# MCU.net
KiCad netlist of a schematic drawn in Altium Designer
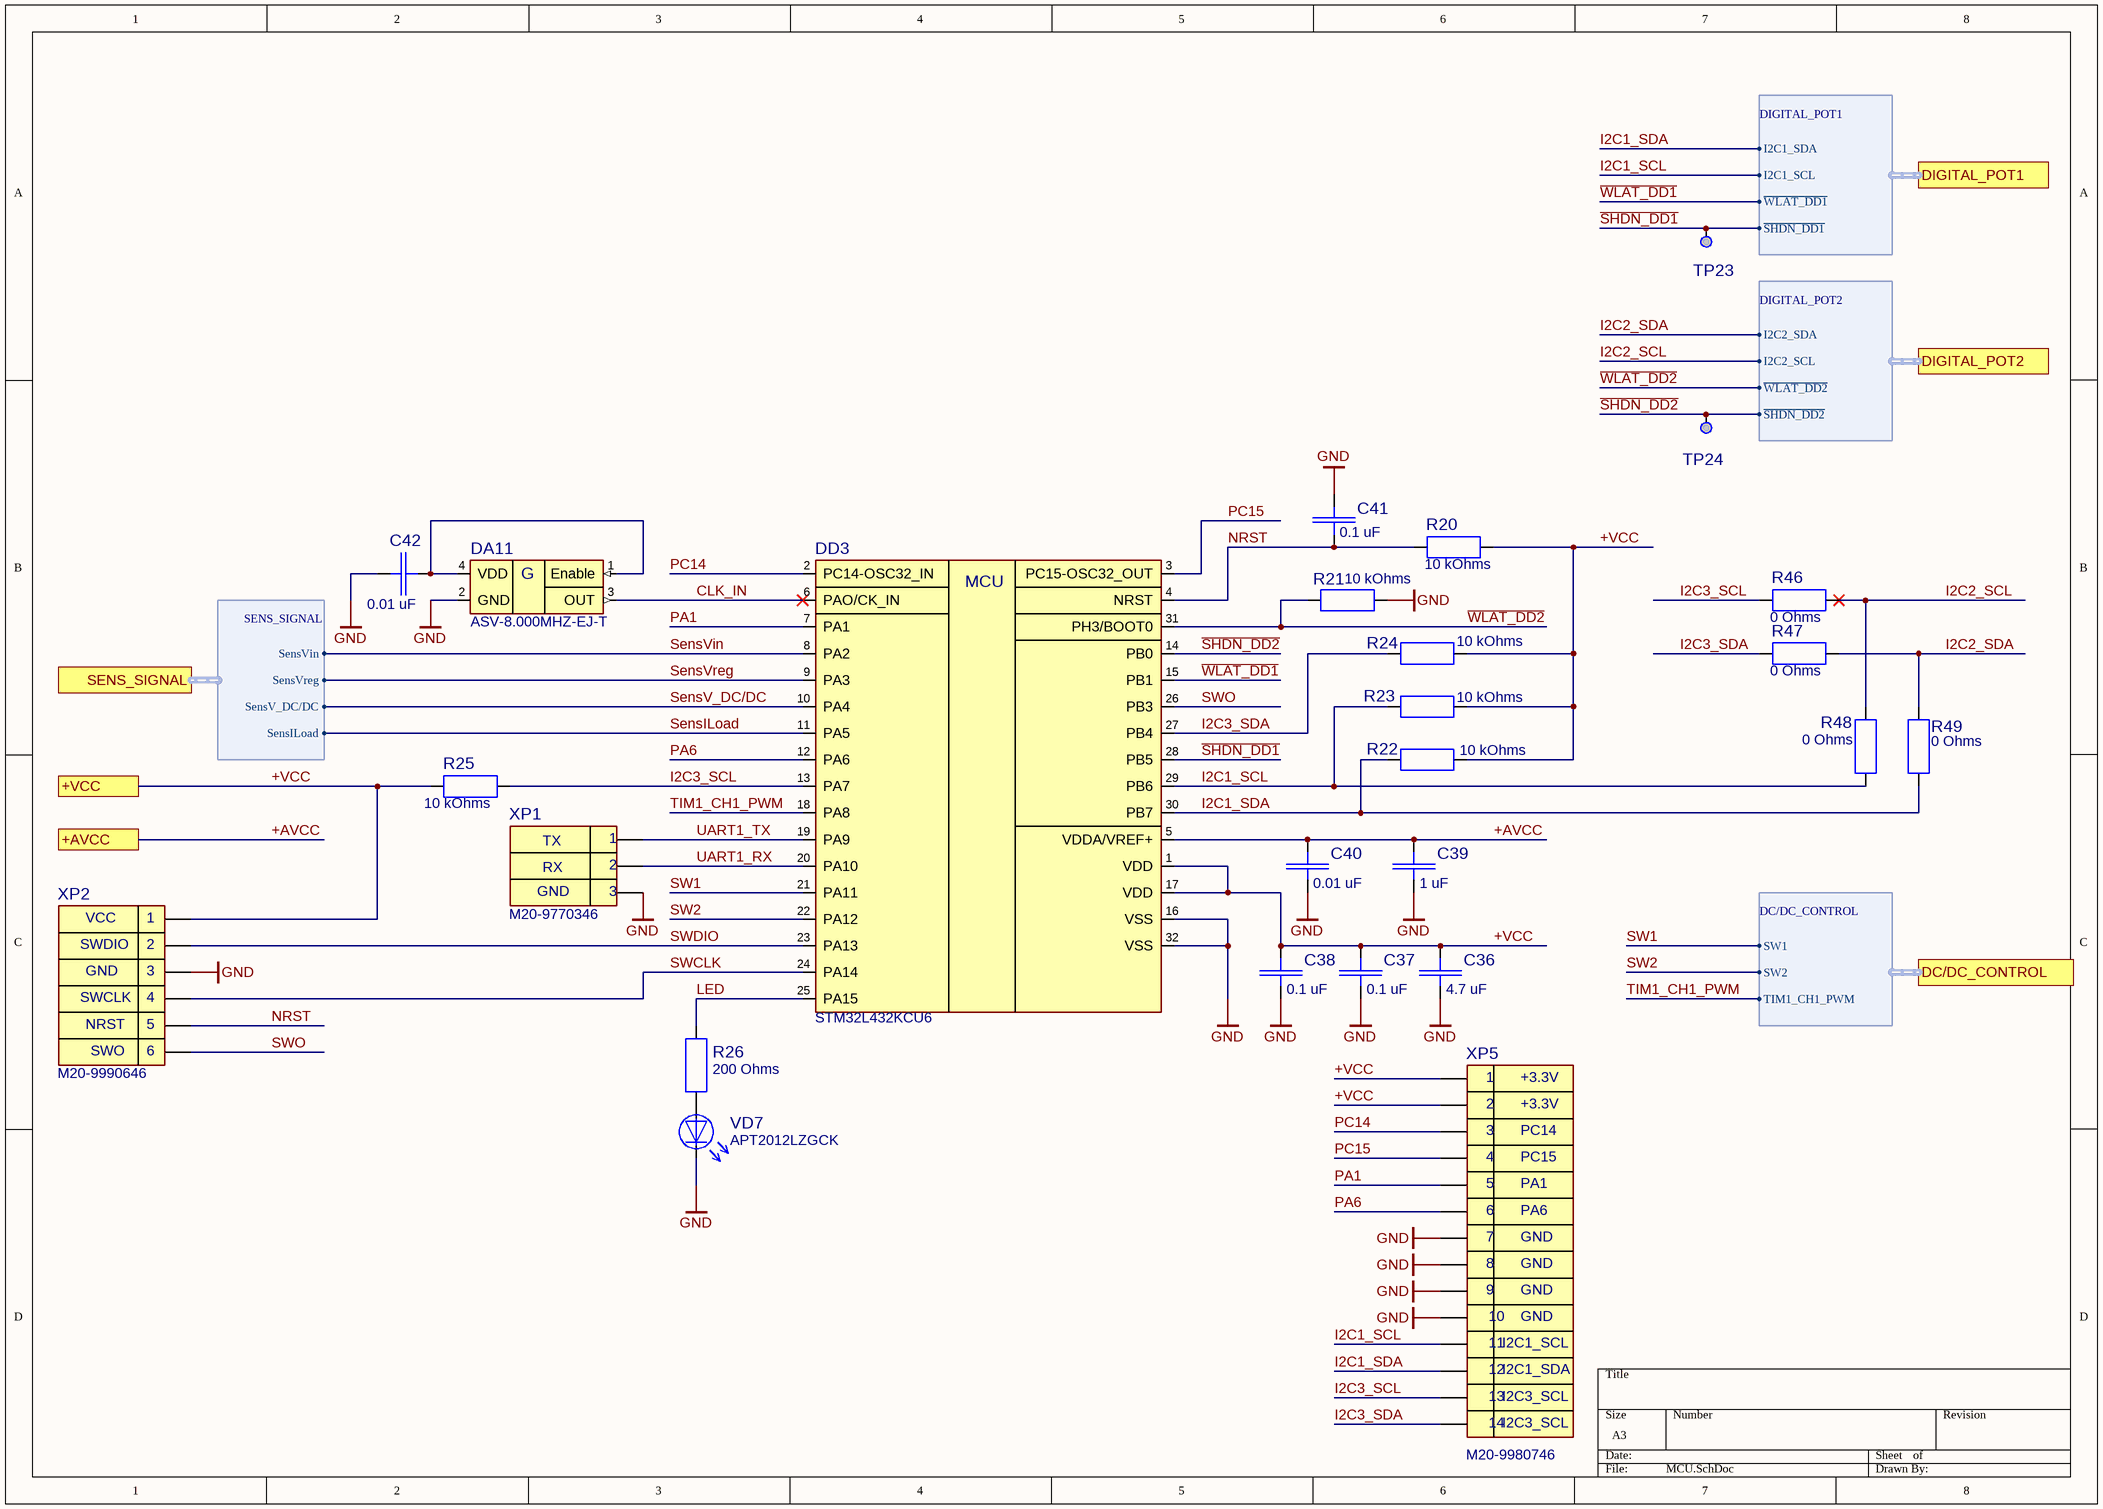
[diagram p0: MCU.SchDoc]

(export (version "E")
  (design (tool "Eeschema 10.0.6"))
  (components
    (comp (ref "C36")
      (value "4.7 uF")
      (footprint "Capacitor0805_THICKNESS1.25")
      (description "Multilayer Ceramic Capacitors MLCC - SMD/SMT 4.7uF+/-10% 25V X5R 0805")
      (fields
        (field (name "MANUFACTURER") "Samsung Electro-Mechanics")
        (field (name "MANUFACTURERPARTNUMBER") "CL21A475KAQNNNF")
      )
      (libsource (lib "NGI_Search") (part "CL21A475KAQNNNF"))
    )
    (comp (ref "C37")
      (value "0.1 uF")
      (footprint "Capacitor0805_THICKNESS0.8")
      (description "Multilayer Ceramic Capacitors MLCC - SMD/SMT 100nF+/-10% 50V X7R 0805")
      (fields (field (name "TOLERANCE") "10%") (field (name "MANUFACTURERPARTNUMBER") "CL21B104KBCNNWC"))
      (libsource (lib "NGI_Search") (part "CL21B104KBCNNWC"))
    )
    (comp (ref "C38")
      (value "0.1 uF")
      (footprint "Capacitor0805_THICKNESS0.8")
      (description "Multilayer Ceramic Capacitors MLCC - SMD/SMT 100nF+/-10% 50V X7R 0805")
      (fields (field (name "TOLERANCE") "10%") (field (name "MANUFACTURERPARTNUMBER") "CL21B104KBCNNWC"))
      (libsource (lib "NGI_Search") (part "CL21B104KBCNNWC"))
    )
    (comp (ref "C39")
      (value "1 uF")
      (footprint "Capacitor0805_THICKNESS1.25")
      (description "Multilayer Ceramic Capacitors MLCC - SMD/SMT 1uF+/-10% 25V X7R 20 0805")
      (fields
        (field (name "MANUFACTURER") "Samsung Electro-Mechanics")
        (field (name "MANUFACTURERPARTNUMBER") "CL21B105KAFNFNE")
      )
      (libsource (lib "NGI_Search") (part "CL21B105KAFNFNE"))
    )
    (comp (ref "C40")
      (value "0.01 uF")
      (footprint "Capacitor0805_THICKNESS0.8")
      (description "Multilayer Ceramic Capacitors MLCC - SMD/SMT 10nF+/-10% 50V X7R 2 0805")
      (fields
        (field (name "MANUFACTURER") "Samsung Electro-Mechanics")
        (field (name "MANUFACTURERPARTNUMBER") "CL21B103KBANNNL")
      )
      (libsource (lib "NGI_Search") (part "CL21B103KBANNNL"))
    )
    (comp (ref "C41")
      (value "0.1 uF")
      (footprint "Capacitor0805_THICKNESS0.8")
      (description "Multilayer Ceramic Capacitors MLCC - SMD/SMT 100nF+/-10% 50V X7R 0805")
      (fields (field (name "TOLERANCE") "10%") (field (name "MANUFACTURERPARTNUMBER") "CL21B104KBCNNWC"))
      (libsource (lib "NGI_Search") (part "CL21B104KBCNNWC"))
    )
    (comp (ref "C42")
      (value "0.01 uF")
      (footprint "Capacitor0805_THICKNESS0.8")
      (description "Multilayer Ceramic Capacitors MLCC - SMD/SMT 10nF+/-10% 50V X7R 2 0805")
      (fields
        (field (name "MANUFACTURER") "Samsung Electro-Mechanics")
        (field (name "MANUFACTURERPARTNUMBER") "CL21B103KBANNNL")
      )
      (libsource (lib "NGI_Search") (part "CL21B103KBANNNL"))
    )
    (comp (ref "DA11")
      (value "ASV-8.000MHZ-EJ-T")
      (footprint "HCMOS 7 mm x 5 mm")
      (description "Standard Clock Oscillators XTAL OSC XO 8.0000MHZ HCMOS SMD")
      (fields (field (name "MANUFACTURER") "ABRACON") (field (name "MOUSER PART NUMBER") "815-ASV-8-EJ-T"))
      (libsource (lib "NGI_Search") (part "ASV-8.000MHZ-EJ-T"))
    )
    (comp (ref "DD3")
      (value "STM32L432KCU6")
      (footprint "UFQFPN-32")
      (description "ARM Microcontrollers - MCU Ultra-low-power FPU Arm Cortex-M4 MCU 80 MHz 256 Kbytes of Flash , USB")
      (fields
        (field (name "MANUFACTURER") "STMicroelectronics")
        (field (name "MOUSER PART NUMBER") "511-STM32L432KCU6")
      )
      (libsource (lib "NGI_Search") (part "STM32L432KCU6"))
    )
    (comp (ref "R20")
      (value "10 kOhms")
      (footprint "Resistor0805_THICKNESS0.6")
      (description "Thick Film Resistors 10 kOhms 125 mW 0805 1%")
      (fields (field (name "MANUFACTURER") "YAGEO") (field (name "MANUFACTURERPARTNUMBER") "RC0805FR-0710KL"))
      (libsource (lib "NGI_Search") (part "RC0805FR-0710KL"))
    )
    (comp (ref "R21")
      (value "10 kOhms")
      (footprint "Resistor0805_THICKNESS0.6")
      (description "Thick Film Resistors 10 kOhms 125 mW 0805 1%")
      (fields (field (name "MANUFACTURER") "YAGEO") (field (name "MANUFACTURERPARTNUMBER") "RC0805FR-0710KL"))
      (libsource (lib "NGI_Search") (part "RC0805FR-0710KL"))
    )
    (comp (ref "R22")
      (value "10 kOhms")
      (footprint "Resistor0805_THICKNESS0.6")
      (description "Thick Film Resistors 10 kOhms 125 mW 0805 1%")
      (fields (field (name "MANUFACTURER") "YAGEO") (field (name "MANUFACTURERPARTNUMBER") "RC0805FR-0710KL"))
      (libsource (lib "NGI_Search") (part "RC0805FR-0710KL"))
    )
    (comp (ref "R23")
      (value "10 kOhms")
      (footprint "Resistor0805_THICKNESS0.6")
      (description "Thick Film Resistors 10 kOhms 125 mW 0805 1%")
      (fields (field (name "MANUFACTURER") "YAGEO") (field (name "MANUFACTURERPARTNUMBER") "RC0805FR-0710KL"))
      (libsource (lib "NGI_Search") (part "RC0805FR-0710KL"))
    )
    (comp (ref "R24")
      (value "10 kOhms")
      (footprint "Resistor0805_THICKNESS0.6")
      (description "Thick Film Resistors 10 kOhms 125 mW 0805 1%")
      (fields (field (name "MANUFACTURER") "YAGEO") (field (name "MANUFACTURERPARTNUMBER") "RC0805FR-0710KL"))
      (libsource (lib "NGI_Search") (part "RC0805FR-0710KL"))
    )
    (comp (ref "R25")
      (value "10 kOhms")
      (footprint "Resistor0805_THICKNESS0.6")
      (description "Thick Film Resistors 10 kOhms 125 mW 0805 1%")
      (fields (field (name "MANUFACTURER") "YAGEO") (field (name "MANUFACTURERPARTNUMBER") "RC0805FR-0710KL"))
      (libsource (lib "NGI_Search") (part "RC0805FR-0710KL"))
    )
    (comp (ref "R26")
      (value "200 Ohms")
      (footprint "Resistor0805_THICKNESS0.6")
      (description "Thick Film Resistors 200Ohms 1/8W 0805 1%")
      (fields
        (field (name "MANUFACTURER") "YAGEO")
        (field (name "MANUFACTURERPARTNUMBER") "RC0805FR-10200RL")
      )
      (libsource (lib "NGI_Search") (part "RC0805FR-10200RL"))
    )
    (comp (ref "R46")
      (value "0 Ohms")
      (footprint "Resistor0805_THICKNESS0.6")
      (description "Thick Film Resistors 0 Ohms 125 mW 0805 1%")
      (fields (field (name "MANUFACTURER") "YAGEO") (field (name "MANUFACTURERPARTNUMBER") "RC0805FR-070RL"))
      (libsource (lib "NGI_Search") (part "RC0805FR-070RL"))
    )
    (comp (ref "R47")
      (value "0 Ohms")
      (footprint "Resistor0805_THICKNESS0.6")
      (description "Thick Film Resistors 0 Ohms 125 mW 0805 1%")
      (fields (field (name "MANUFACTURER") "YAGEO") (field (name "MANUFACTURERPARTNUMBER") "RC0805FR-070RL"))
      (libsource (lib "NGI_Search") (part "RC0805FR-070RL"))
    )
    (comp (ref "R48")
      (value "0 Ohms")
      (footprint "Resistor0805_THICKNESS0.6")
      (description "Thick Film Resistors 0 Ohms 125 mW 0805 1%")
      (fields (field (name "MANUFACTURER") "YAGEO") (field (name "MANUFACTURERPARTNUMBER") "RC0805FR-070RL"))
      (libsource (lib "NGI_Search") (part "RC0805FR-070RL"))
    )
    (comp (ref "R49")
      (value "0 Ohms")
      (footprint "Resistor0805_THICKNESS0.6")
      (description "Thick Film Resistors 0 Ohms 125 mW 0805 1%")
      (fields (field (name "MANUFACTURER") "YAGEO") (field (name "MANUFACTURERPARTNUMBER") "RC0805FR-070RL"))
      (libsource (lib "NGI_Search") (part "RC0805FR-070RL"))
    )
    (comp (ref "TP23")
      (value "test point")
      (footprint "test point")
      (libsource (lib "NGI_Search") (part "test point"))
    )
    (comp (ref "TP24")
      (value "test point")
      (footprint "test point")
      (libsource (lib "NGI_Search") (part "test point"))
    )
    (comp (ref "VD7")
      (value "APT2012LZGCK")
      (footprint "APT2012LZGCK0805_LEDs")
      (description "Standard LEDs - SMD 2.0X1.2MM LOW CRNT")
      (fields
        (field (name "MANUFACTURER") "Kingbright")
        (field (name "MOUSER PART NUMBER") "604-APT2012LZGCK")
      )
      (libsource (lib "NGI_Search") (part "APT2012LZGCK"))
    )
    (comp (ref "XP1")
      (value "M20-9770346")
      (footprint "3 VERTICAL PIN Pitch: 2.54 mm")
      (description "Headers & Wire Housings 03 SIL VERTICAL PIN HEADER TIN")
      (fields (field (name "MANUFACTURER") "Harwin") (field (name "MOUSER PART NUMBER") "855-M20-9770346"))
      (libsource (lib "NGI_Search") (part "M20-9770346"))
    )
    (comp (ref "XP2")
      (value "M20-9990646")
      (footprint "6 VERTICAL PIN Pitch: 2.54 mm")
      (description "Headers & Wire Housings 06 SIL VERTICAL PIN HEADER TIN")
      (fields (field (name "MANUFACTURER") "Harwin"))
      (libsource (lib "NGI_Search") (part "M20-9990646"))
    )
    (comp (ref "XP5")
      (value "M20-9980746")
      (footprint "M20-9980746")
      (description "Headers & Wire Housings 07+07 DIL VERTICAL PIN HEADER TIN")
      (fields (field (name "MANUFACTURER") "Harwin") (field (name "MOUSER PART NUMBER") "855-M20-9980746"))
      (libsource (lib "NGI_Search") (part "M20-9980746"))
    )
  )
  (nets
    (net (code "5") (name "/+AVCC") (class "Default")
      (node (ref "C39") (pin "2") (pinfunction "2_2") (pintype "passive"))
      (node (ref "C40") (pin "2") (pinfunction "2_2") (pintype "passive"))
      (node (ref "DD3") (pin "5") (pinfunction "VDDA/VREF+_5") (pintype "power_in"))
    )
    (net (code "6") (name "/+VCC") (class "Default")
      (node (ref "C36") (pin "2") (pinfunction "2_2") (pintype "passive"))
      (node (ref "C37") (pin "2") (pinfunction "2_2") (pintype "passive"))
      (node (ref "C38") (pin "2") (pinfunction "2_2") (pintype "passive"))
      (node (ref "DD3") (pin "1") (pinfunction "VDD_1") (pintype "power_in"))
      (node (ref "DD3") (pin "17") (pinfunction "VDD_17") (pintype "power_in"))
      (node (ref "R20") (pin "2") (pinfunction "2_2") (pintype "passive"))
      (node (ref "R22") (pin "1") (pinfunction "1_1") (pintype "passive"))
      (node (ref "R23") (pin "2") (pinfunction "2_2") (pintype "passive"))
      (node (ref "R24") (pin "1") (pinfunction "1_1") (pintype "passive"))
      (node (ref "R25") (pin "1") (pinfunction "1_1") (pintype "passive"))
      (node (ref "XP2") (pin "1") (pintype "passive"))
      (node (ref "XP5") (pin "1") (pintype "passive"))
      (node (ref "XP5") (pin "2") (pintype "passive"))
    )
    (net (code "7") (name "/CLK_IN") (class "Default")
      (node (ref "DA11") (pin "3") (pinfunction "OUT_3") (pintype "output"))
      (node (ref "DD3") (pin "6") (pinfunction "PAO/CK_IN_6") (pintype "bidirectional"))
    )
    (net (code "8") (name "/I2C1_SCL") (class "Default")
      (node (ref "DD3") (pin "29") (pinfunction "PB6_29") (pintype "bidirectional"))
      (node (ref "R23") (pin "1") (pinfunction "1_1") (pintype "passive"))
      (node (ref "R48") (pin "1") (pinfunction "1_1") (pintype "passive"))
      (node (ref "XP5") (pin "11") (pinfunction "11_11") (pintype "passive"))
    )
    (net (code "9") (name "/I2C1_SDA") (class "Default")
      (node (ref "DD3") (pin "30") (pinfunction "PB7_30") (pintype "bidirectional"))
      (node (ref "R22") (pin "2") (pinfunction "2_2") (pintype "passive"))
      (node (ref "R49") (pin "1") (pinfunction "1_1") (pintype "passive"))
      (node (ref "XP5") (pin "12") (pinfunction "12_12") (pintype "passive"))
    )
    (net (code "10") (name "/I2C2_SCL") (class "Default")
      (node (ref "R46") (pin "2") (pinfunction "2_2") (pintype "passive"))
      (node (ref "R48") (pin "2") (pinfunction "2_2") (pintype "passive"))
    )
    (net (code "11") (name "/I2C2_SDA") (class "Default")
      (node (ref "R47") (pin "2") (pinfunction "2_2") (pintype "passive"))
      (node (ref "R49") (pin "2") (pinfunction "2_2") (pintype "passive"))
    )
    (net (code "12") (name "/I2C3_SCL") (class "Default")
      (node (ref "DD3") (pin "13") (pinfunction "PA7_13") (pintype "bidirectional"))
      (node (ref "R25") (pin "2") (pinfunction "2_2") (pintype "passive"))
      (node (ref "R46") (pin "1") (pinfunction "1_1") (pintype "passive"))
      (node (ref "XP5") (pin "13") (pinfunction "13_13") (pintype "passive"))
    )
    (net (code "13") (name "/I2C3_SDA") (class "Default")
      (node (ref "DD3") (pin "27") (pinfunction "PB4_27") (pintype "bidirectional"))
      (node (ref "R24") (pin "2") (pinfunction "2_2") (pintype "passive"))
      (node (ref "R47") (pin "1") (pinfunction "1_1") (pintype "passive"))
      (node (ref "XP5") (pin "14") (pinfunction "14_14") (pintype "passive"))
    )
    (net (code "14") (name "/LED") (class "Default")
      (node (ref "DD3") (pin "25") (pinfunction "PA15_25") (pintype "bidirectional"))
      (node (ref "R26") (pin "2") (pinfunction "2_2") (pintype "passive"))
    )
    (net (code "15") (name "/NRST") (class "Default")
      (node (ref "C41") (pin "2") (pinfunction "2_2") (pintype "passive"))
      (node (ref "DD3") (pin "4") (pinfunction "NRST_4") (pintype "bidirectional"))
      (node (ref "R20") (pin "1") (pinfunction "1_1") (pintype "passive"))
      (node (ref "XP2") (pin "5") (pintype "passive"))
    )
    (net (code "16") (name "/PA1") (class "Default")
      (node (ref "DD3") (pin "7") (pinfunction "PA1_7") (pintype "bidirectional"))
      (node (ref "XP5") (pin "5") (pintype "passive"))
    )
    (net (code "17") (name "/PA6") (class "Default")
      (node (ref "DD3") (pin "12") (pinfunction "PA6_12") (pintype "bidirectional"))
      (node (ref "XP5") (pin "6") (pintype "passive"))
    )
    (net (code "18") (name "/PC14") (class "Default")
      (node (ref "DD3") (pin "2") (pinfunction "PC14-OSC32_IN_2") (pintype "bidirectional"))
      (node (ref "XP5") (pin "3") (pintype "passive"))
    )
    (net (code "19") (name "/PC15") (class "Default")
      (node (ref "DD3") (pin "3") (pinfunction "PC15-OSC32_OUT_3") (pintype "bidirectional"))
      (node (ref "XP5") (pin "4") (pintype "passive"))
    )
    (net (code "20") (name "/SW1") (class "Default")
      (node (ref "DD3") (pin "21") (pinfunction "PA11_21") (pintype "bidirectional"))
    )
    (net (code "21") (name "/SW2") (class "Default")
      (node (ref "DD3") (pin "22") (pinfunction "PA12_22") (pintype "bidirectional"))
    )
    (net (code "22") (name "/SWCLK") (class "Default")
      (node (ref "DD3") (pin "24") (pinfunction "PA14_24") (pintype "bidirectional"))
      (node (ref "XP2") (pin "4") (pintype "passive"))
    )
    (net (code "23") (name "/SWDIO") (class "Default")
      (node (ref "DD3") (pin "23") (pinfunction "PA13_23") (pintype "bidirectional"))
      (node (ref "XP2") (pin "2") (pintype "passive"))
    )
    (net (code "24") (name "/SWO") (class "Default")
      (node (ref "DD3") (pin "26") (pinfunction "PB3_26") (pintype "bidirectional"))
      (node (ref "XP2") (pin "6") (pintype "passive"))
    )
    (net (code "25") (name "/SensILoad") (class "Default")
      (node (ref "DD3") (pin "11") (pinfunction "PA5_11") (pintype "bidirectional"))
    )
    (net (code "26") (name "/SensV_DC{slash}DC") (class "Default")
      (node (ref "DD3") (pin "10") (pinfunction "PA4_10") (pintype "bidirectional"))
    )
    (net (code "27") (name "/SensVin") (class "Default")
      (node (ref "DD3") (pin "8") (pinfunction "PA2_8") (pintype "bidirectional"))
    )
    (net (code "28") (name "/SensVreg") (class "Default")
      (node (ref "DD3") (pin "9") (pinfunction "PA3_9") (pintype "bidirectional"))
    )
    (net (code "29") (name "/TIM1_CH1_PWM") (class "Default")
      (node (ref "DD3") (pin "18") (pinfunction "PA8_18") (pintype "bidirectional"))
    )
    (net (code "30") (name "/UART1_RX") (class "Default")
      (node (ref "DD3") (pin "20") (pinfunction "PA10_20") (pintype "bidirectional"))
      (node (ref "XP1") (pin "2") (pintype "passive"))
    )
    (net (code "31") (name "/UART1_TX") (class "Default")
      (node (ref "DD3") (pin "19") (pinfunction "PA9_19") (pintype "bidirectional"))
      (node (ref "XP1") (pin "1") (pintype "passive"))
    )
    (net (code "36") (name "/~{SHDN_DD1}") (class "Default")
      (node (ref "DD3") (pin "28") (pinfunction "PB5_28") (pintype "bidirectional"))
      (node (ref "TP23") (pin "1") (pinfunction "1_1") (pintype "passive"))
    )
    (net (code "37") (name "/~{SHDN_DD2}") (class "Default")
      (node (ref "DD3") (pin "14") (pinfunction "PB0_14") (pintype "bidirectional"))
      (node (ref "TP24") (pin "1") (pinfunction "1_1") (pintype "passive"))
    )
    (net (code "38") (name "/~{WLAT_DD1}") (class "Default")
      (node (ref "DD3") (pin "15") (pinfunction "PB1_15") (pintype "bidirectional"))
    )
    (net (code "39") (name "/~{WLAT_DD2}") (class "Default")
      (node (ref "DD3") (pin "31") (pinfunction "PH3/BOOT0_31") (pintype "bidirectional"))
      (node (ref "R21") (pin "1") (pinfunction "1_1") (pintype "passive"))
    )
    (net (code "40") (name "GND") (class "Default")
      (node (ref "C36") (pin "1") (pinfunction "1_1") (pintype "passive"))
      (node (ref "C37") (pin "1") (pinfunction "1_1") (pintype "passive"))
      (node (ref "C38") (pin "1") (pinfunction "1_1") (pintype "passive"))
      (node (ref "C39") (pin "1") (pinfunction "1_1") (pintype "passive"))
      (node (ref "C40") (pin "1") (pinfunction "1_1") (pintype "passive"))
      (node (ref "C41") (pin "1") (pinfunction "1_1") (pintype "passive"))
      (node (ref "C42") (pin "1") (pinfunction "1_1") (pintype "passive"))
      (node (ref "DA11") (pin "2") (pinfunction "GND_2") (pintype "power_in"))
      (node (ref "DD3") (pin "16") (pinfunction "VSS_16") (pintype "power_in"))
      (node (ref "DD3") (pin "32") (pinfunction "VSS_32") (pintype "power_in"))
      (node (ref "R21") (pin "2") (pinfunction "2_2") (pintype "passive"))
      (node (ref "VD7") (pin "C") (pinfunction "C_C") (pintype "passive"))
      (node (ref "XP1") (pin "3") (pintype "passive"))
      (node (ref "XP2") (pin "3") (pintype "passive"))
      (node (ref "XP5") (pin "10") (pinfunction "10_10") (pintype "passive"))
      (node (ref "XP5") (pin "7") (pinfunction "7_7") (pintype "passive"))
      (node (ref "XP5") (pin "8") (pinfunction "8_8") (pintype "passive"))
      (node (ref "XP5") (pin "9") (pinfunction "9_9") (pintype "passive"))
    )
    (net (code "41") (name "Net-(DA11-Enable)") (class "Default")
      (node (ref "C42") (pin "2") (pinfunction "2_2") (pintype "passive"))
      (node (ref "DA11") (pin "1") (pinfunction "Enable_1") (pintype "input"))
      (node (ref "DA11") (pin "4") (pinfunction "VDD_4") (pintype "power_in"))
    )
    (net (code "42") (name "Net-(R26-Pad1)") (class "Default")
      (node (ref "R26") (pin "1") (pinfunction "1_1") (pintype "passive"))
      (node (ref "VD7") (pin "A") (pinfunction "A_A") (pintype "passive"))
    )
  )
)
